# SCH__-_-__2023-09-22.net
KiCad netlist of a schematic drawn in EasyEDA
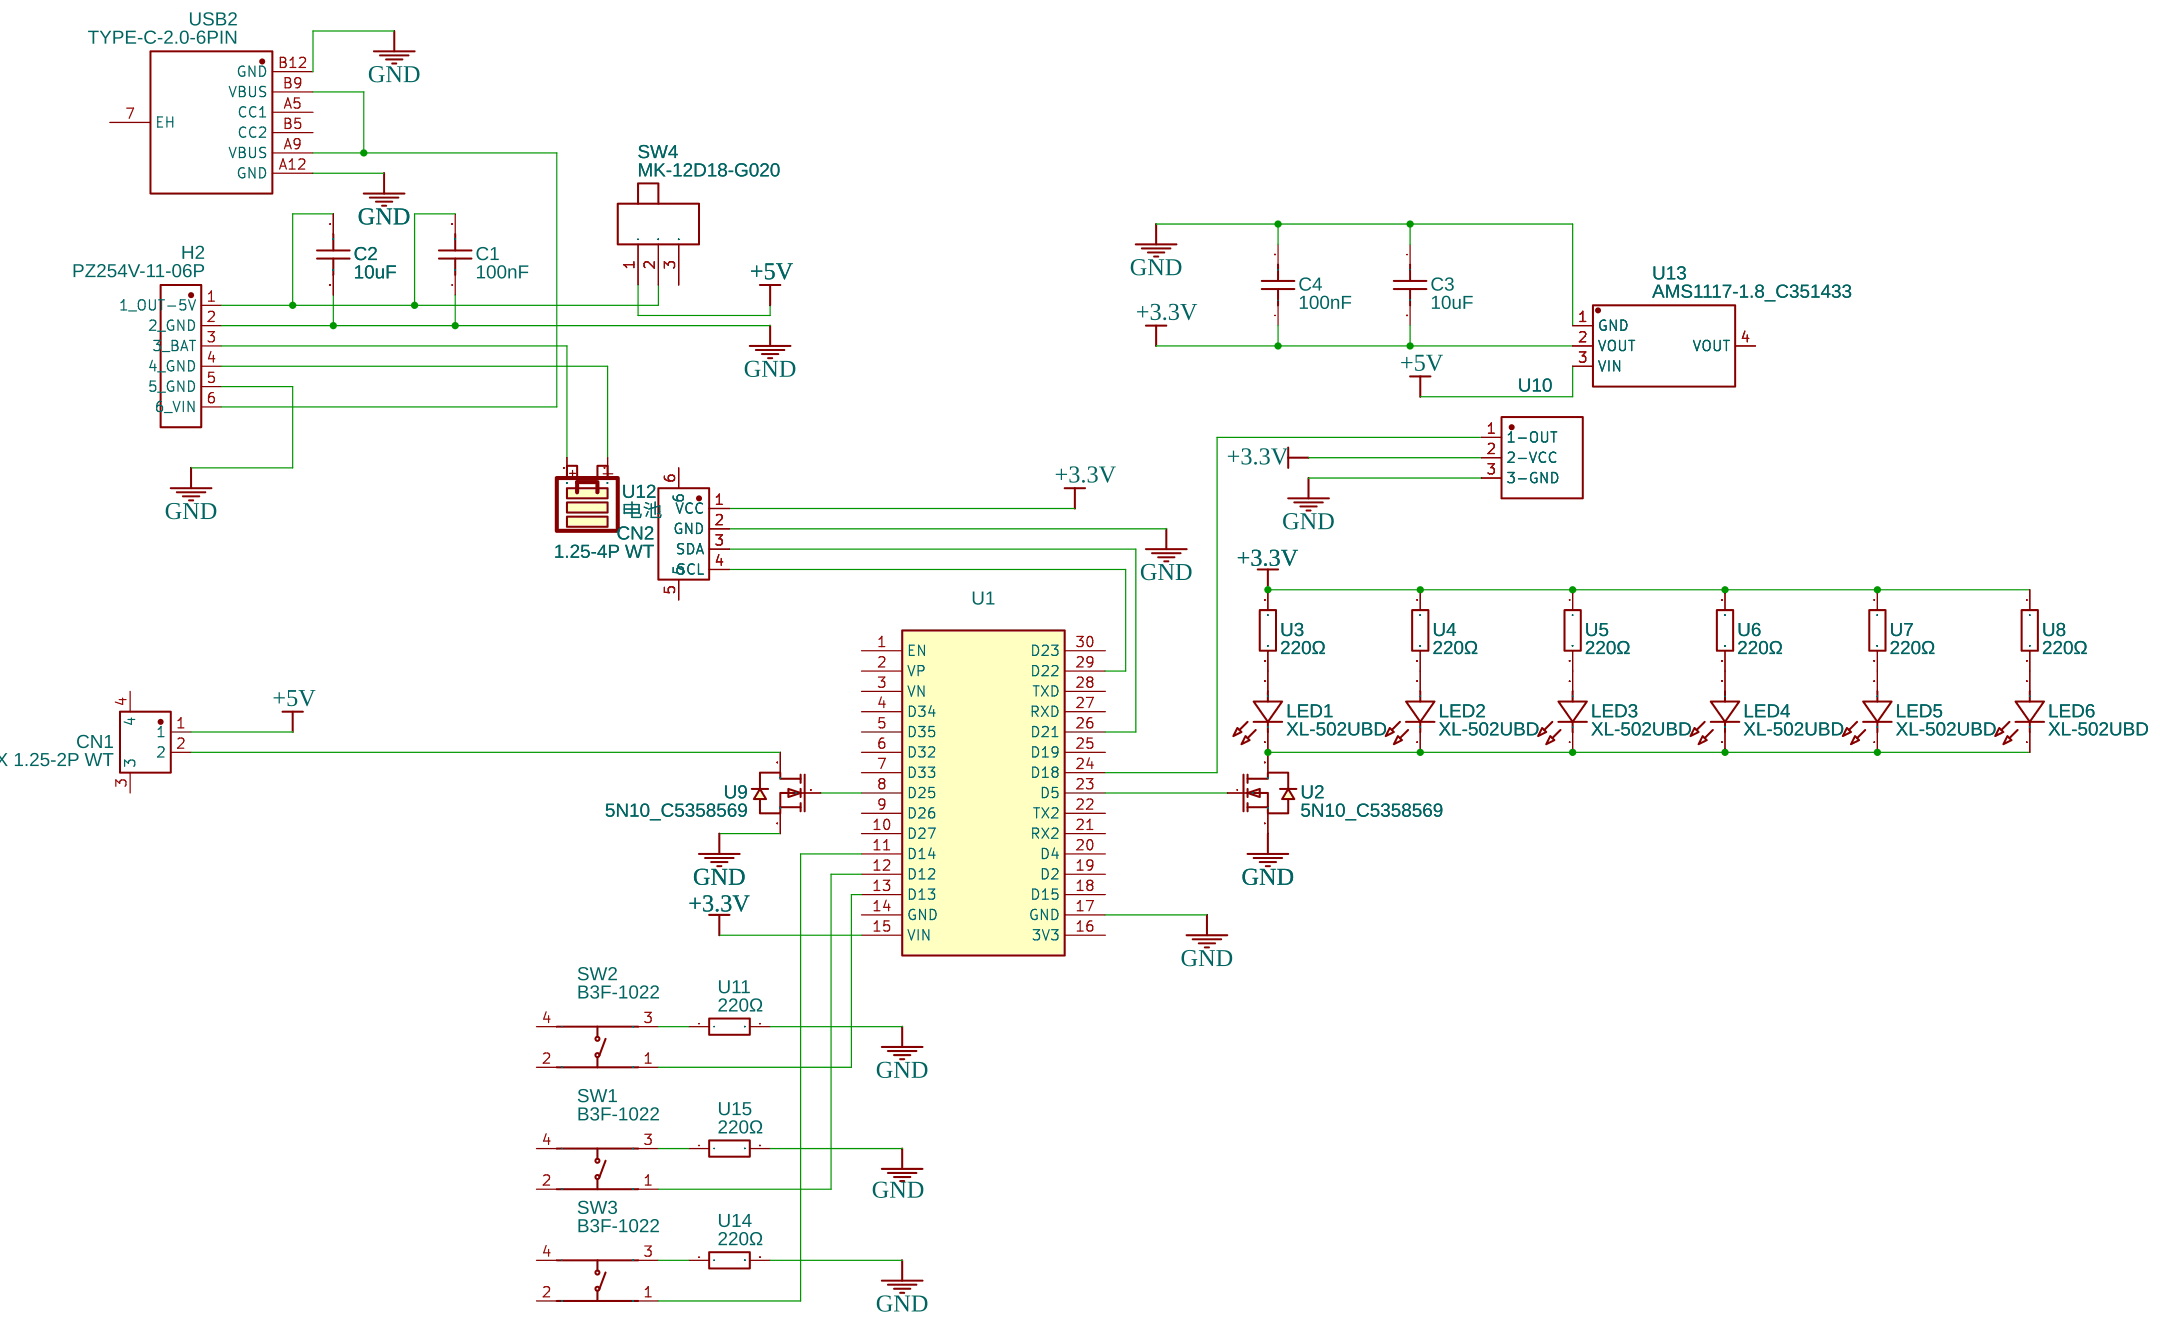
[diagram p0: schematic sheet]

(export (version "E")
  (design (tool "Eeschema 10.0.6"))
  (components
    (comp (ref "C1")
      (value "100nF")
      (fields
        (field (name "Manufacturer Part") "MC0603B104K500N8RH")
        (field (name "Manufacturer") "Sunway(信维通信)")
      )
      (libsource (lib "") (part "MC0603B104K500N8RH"))
    )
    (comp (ref "C2")
      (value "10uF")
      (fields (field (name "Manufacturer") "SAMSUNG(三星)"))
      (libsource (lib "") (part "10UF"))
    )
    (comp (ref "C3")
      (value "10uF")
      (fields (field (name "Manufacturer") "SAMSUNG(三星)"))
      (libsource (lib "") (part "10UF"))
    )
    (comp (ref "C4")
      (value "100nF")
      (fields
        (field (name "Manufacturer Part") "MC0603B104K500N8RH")
        (field (name "Manufacturer") "Sunway(信维通信)")
      )
      (libsource (lib "") (part "MC0603B104K500N8RH"))
    )
    (comp (ref "CN1")
      (value "HX 1.25-2P WT")
      (fields (field (name "Manufacturer") "hanxia(韩下)"))
      (libsource (lib "") (part "HX 1.25-2P WT"))
    )
    (comp (ref "CN2")
      (value "1.25-4P WT")
      (fields (field (name "Manufacturer") "SHOU HAN(首韩)"))
      (libsource (lib "") (part "1.25-4P WT"))
    )
    (comp (ref "H2")
      (value "PZ254V-11-06P")
      (fields (field (name "Manufacturer") "XFCN(兴飞)"))
      (libsource (lib "") (part "PZ254V-11-06P"))
    )
    (comp (ref "LED1")
      (value "XL-502UBD")
      (fields (field (name "Manufacturer") "XINGLIGHT(成兴光)"))
      (libsource (lib "") (part "XL-502UBD"))
    )
    (comp (ref "LED2")
      (value "XL-502UBD")
      (fields (field (name "Manufacturer") "XINGLIGHT(成兴光)"))
      (libsource (lib "") (part "XL-502UBD"))
    )
    (comp (ref "LED3")
      (value "XL-502UBD")
      (fields (field (name "Manufacturer") "XINGLIGHT(成兴光)"))
      (libsource (lib "") (part "XL-502UBD"))
    )
    (comp (ref "LED4")
      (value "XL-502UBD")
      (fields (field (name "Manufacturer") "XINGLIGHT(成兴光)"))
      (libsource (lib "") (part "XL-502UBD"))
    )
    (comp (ref "LED5")
      (value "XL-502UBD")
      (fields (field (name "Manufacturer") "XINGLIGHT(成兴光)"))
      (libsource (lib "") (part "XL-502UBD"))
    )
    (comp (ref "LED6")
      (value "XL-502UBD")
      (fields (field (name "Manufacturer") "XINGLIGHT(成兴光)"))
      (libsource (lib "") (part "XL-502UBD"))
    )
    (comp (ref "SW1")
      (value "B3F-1022")
      (fields (field (name "Manufacturer") "OMRON(欧姆龙)"))
      (libsource (lib "") (part "B3F-1022"))
    )
    (comp (ref "SW2")
      (value "B3F-1022")
      (fields (field (name "Manufacturer") "OMRON(欧姆龙)"))
      (libsource (lib "") (part "B3F-1022"))
    )
    (comp (ref "SW3")
      (value "B3F-1022")
      (fields (field (name "Manufacturer") "OMRON(欧姆龙)"))
      (libsource (lib "") (part "B3F-1022"))
    )
    (comp (ref "SW4")
      (value "MK-12D18-G020")
      (fields (field (name "Manufacturer") "G-Switch(品赞)"))
      (libsource (lib "") (part "MK-12D18-G020"))
    )
    (comp (ref "U1") (value "NO") (libsource (lib "") (part "ESP-WROOM-32")))
    (comp (ref "U2")
      (value "5N10_C5358569")
      (fields (field (name "Manufacturer Part") "5N10") (field (name "Manufacturer") "GOODWORK(固得沃克)"))
      (libsource (lib "") (part "5N10_C5358569_1"))
    )
    (comp (ref "U3")
      (value "220Ω")
      (fields (field (name "Manufacturer Part") "MF1/8W-220Ω±1%-ST52") (field (name "Manufacturer") "VO(翔胜)"))
      (libsource (lib "") (part "MF1/8W-220Ω±1%-ST52"))
    )
    (comp (ref "U4")
      (value "220Ω")
      (fields (field (name "Manufacturer Part") "MF1/8W-220Ω±1%-ST52") (field (name "Manufacturer") "VO(翔胜)"))
      (libsource (lib "") (part "MF1/8W-220Ω±1%-ST52"))
    )
    (comp (ref "U5")
      (value "220Ω")
      (fields (field (name "Manufacturer Part") "MF1/8W-220Ω±1%-ST52") (field (name "Manufacturer") "VO(翔胜)"))
      (libsource (lib "") (part "MF1/8W-220Ω±1%-ST52"))
    )
    (comp (ref "U6")
      (value "220Ω")
      (fields (field (name "Manufacturer Part") "MF1/8W-220Ω±1%-ST52") (field (name "Manufacturer") "VO(翔胜)"))
      (libsource (lib "") (part "MF1/8W-220Ω±1%-ST52"))
    )
    (comp (ref "U7")
      (value "220Ω")
      (fields (field (name "Manufacturer Part") "MF1/8W-220Ω±1%-ST52") (field (name "Manufacturer") "VO(翔胜)"))
      (libsource (lib "") (part "MF1/8W-220Ω±1%-ST52"))
    )
    (comp (ref "U8")
      (value "220Ω")
      (fields (field (name "Manufacturer Part") "MF1/8W-220Ω±1%-ST52") (field (name "Manufacturer") "VO(翔胜)"))
      (libsource (lib "") (part "MF1/8W-220Ω±1%-ST52"))
    )
    (comp (ref "U9")
      (value "5N10_C5358569")
      (fields (field (name "Manufacturer Part") "5N10") (field (name "Manufacturer") "GOODWORK(固得沃克)"))
      (libsource (lib "") (part "5N10_C5358569"))
    )
    (comp (ref "U10") (value "NO") (libsource (lib "") (part "SR602")))
    (comp (ref "U11")
      (value "220Ω")
      (fields (field (name "Manufacturer Part") "MF1/8W-220Ω±1%-ST52") (field (name "Manufacturer") "VO(翔胜)"))
      (libsource (lib "") (part "MF1/8W-220Ω±1%-ST52_1"))
    )
    (comp (ref "U12") (value "电池") (libsource (lib "") (part "电池")))
    (comp (ref "U13")
      (value "AMS1117-1.8_C351433")
      (fields (field (name "Manufacturer Part") "AMS1117-1.8") (field (name "Manufacturer") "PUOLOP(迪浦)"))
      (libsource (lib "") (part "AMS1117-1.8_C351433"))
    )
    (comp (ref "U14")
      (value "220Ω")
      (fields (field (name "Manufacturer Part") "MF1/8W-220Ω±1%-ST52") (field (name "Manufacturer") "VO(翔胜)"))
      (libsource (lib "") (part "MF1/8W-220Ω±1%-ST52_1"))
    )
    (comp (ref "U15")
      (value "220Ω")
      (fields (field (name "Manufacturer Part") "MF1/8W-220Ω±1%-ST52") (field (name "Manufacturer") "VO(翔胜)"))
      (libsource (lib "") (part "MF1/8W-220Ω±1%-ST52_1"))
    )
    (comp (ref "USB2")
      (value "TYPE-C-2.0-6PIN")
      (fields (field (name "Manufacturer Part") "Type-C-2.0-6Pin") (field (name "Manufacturer") "CIKI(皓富)"))
      (libsource (lib "") (part "TYPE-C-2.0-6PIN"))
    )
  )
  (nets
    (net (code "1") (name "+3.3V") (class "Default")
      (node (ref "C3") (pin "2") (pinfunction "2_2") (pintype "unspecified"))
      (node (ref "C4") (pin "1") (pinfunction "1_1") (pintype "unspecified"))
      (node (ref "CN2") (pin "1") (pinfunction "VCC_1") (pintype "unspecified"))
      (node (ref "U1") (pin "15") (pinfunction "VIN_15") (pintype "unspecified"))
      (node (ref "U10") (pin "2") (pinfunction "2-VCC_2") (pintype "unspecified"))
      (node (ref "U13") (pin "2") (pinfunction "VOUT_2") (pintype "unspecified"))
      (node (ref "U3") (pin "1") (pinfunction "1_1") (pintype "unspecified"))
      (node (ref "U4") (pin "1") (pinfunction "1_1") (pintype "unspecified"))
      (node (ref "U5") (pin "1") (pinfunction "1_1") (pintype "unspecified"))
      (node (ref "U6") (pin "1") (pinfunction "1_1") (pintype "unspecified"))
      (node (ref "U7") (pin "1") (pinfunction "1_1") (pintype "unspecified"))
      (node (ref "U8") (pin "1") (pinfunction "1_1") (pintype "unspecified"))
    )
    (net (code "2") (name "+5V") (class "Default")
      (node (ref "CN1") (pin "1") (pinfunction "1_1") (pintype "unspecified"))
      (node (ref "SW4") (pin "1") (pinfunction "1_1") (pintype "unspecified"))
      (node (ref "U13") (pin "3") (pinfunction "VIN_3") (pintype "unspecified"))
    )
    (net (code "3") (name "GND") (class "Default")
      (node (ref "C1") (pin "1") (pinfunction "1_1") (pintype "unspecified"))
      (node (ref "C2") (pin "2") (pinfunction "2_2") (pintype "unspecified"))
      (node (ref "C3") (pin "1") (pinfunction "1_1") (pintype "unspecified"))
      (node (ref "C4") (pin "2") (pinfunction "2_2") (pintype "unspecified"))
      (node (ref "CN2") (pin "2") (pinfunction "GND_2") (pintype "unspecified"))
      (node (ref "H2") (pin "2") (pinfunction "2_GND_2") (pintype "unspecified"))
      (node (ref "H2") (pin "5") (pinfunction "5_GND_5") (pintype "unspecified"))
      (node (ref "U1") (pin "17") (pinfunction "GND_17") (pintype "unspecified"))
      (node (ref "U10") (pin "3") (pinfunction "3-GND_3") (pintype "unspecified"))
      (node (ref "U11") (pin "2") (pinfunction "2_2") (pintype "unspecified"))
      (node (ref "U13") (pin "1") (pinfunction "GND_1") (pintype "unspecified"))
      (node (ref "U14") (pin "2") (pinfunction "2_2") (pintype "unspecified"))
      (node (ref "U15") (pin "2") (pinfunction "2_2") (pintype "unspecified"))
      (node (ref "U2") (pin "2") (pinfunction "S_2") (pintype "unspecified"))
      (node (ref "U9") (pin "2") (pinfunction "S_2") (pintype "unspecified"))
      (node (ref "USB2") (pin "A12") (pinfunction "GND_A12") (pintype "unspecified"))
      (node (ref "USB2") (pin "B12") (pinfunction "GND_B12") (pintype "unspecified"))
    )
    (net (code "4") (name "Net-(CN2-SCL)") (class "Default")
      (node (ref "CN2") (pin "4") (pinfunction "SCL_4") (pintype "unspecified"))
      (node (ref "U1") (pin "29") (pinfunction "D22_29") (pintype "unspecified"))
    )
    (net (code "5") (name "Net-(CN2-SDA)") (class "Default")
      (node (ref "CN2") (pin "3") (pinfunction "SDA_3") (pintype "unspecified"))
      (node (ref "U1") (pin "26") (pinfunction "D21_26") (pintype "unspecified"))
    )
    (net (code "6") (name "Net-(H2-1_OUT-5V)") (class "Default")
      (node (ref "C1") (pin "2") (pinfunction "2_2") (pintype "unspecified"))
      (node (ref "C2") (pin "1") (pinfunction "1_1") (pintype "unspecified"))
      (node (ref "H2") (pin "1") (pinfunction "1_OUT-5V_1") (pintype "unspecified"))
      (node (ref "SW4") (pin "2") (pinfunction "2_2") (pintype "unspecified"))
    )
    (net (code "7") (name "Net-(H2-3_BAT)") (class "Default")
      (node (ref "H2") (pin "3") (pinfunction "3_BAT_3") (pintype "unspecified"))
      (node (ref "U12") (pin "1") (pinfunction "1_1") (pintype "unspecified"))
    )
    (net (code "8") (name "Net-(H2-4_GND)") (class "Default")
      (node (ref "H2") (pin "4") (pinfunction "4_GND_4") (pintype "unspecified"))
      (node (ref "U12") (pin "2") (pinfunction "2_2") (pintype "unspecified"))
    )
    (net (code "9") (name "Net-(H2-6_VIN)") (class "Default")
      (node (ref "H2") (pin "6") (pinfunction "6_VIN_6") (pintype "unspecified"))
      (node (ref "USB2") (pin "A9") (pinfunction "VBUS_A9") (pintype "unspecified"))
      (node (ref "USB2") (pin "B9") (pinfunction "VBUS_B9") (pintype "unspecified"))
    )
    (net (code "10") (name "Net-(LED1-A)") (class "Default")
      (node (ref "LED1") (pin "2") (pinfunction "A_2") (pintype "unspecified"))
      (node (ref "U3") (pin "2") (pinfunction "2_2") (pintype "unspecified"))
    )
    (net (code "11") (name "Net-(LED1-K)") (class "Default")
      (node (ref "LED1") (pin "1") (pinfunction "K_1") (pintype "unspecified"))
      (node (ref "LED2") (pin "1") (pinfunction "K_1") (pintype "unspecified"))
      (node (ref "LED3") (pin "1") (pinfunction "K_1") (pintype "unspecified"))
      (node (ref "LED4") (pin "1") (pinfunction "K_1") (pintype "unspecified"))
      (node (ref "LED5") (pin "1") (pinfunction "K_1") (pintype "unspecified"))
      (node (ref "LED6") (pin "1") (pinfunction "K_1") (pintype "unspecified"))
      (node (ref "U2") (pin "3") (pinfunction "D_3") (pintype "unspecified"))
    )
    (net (code "12") (name "Net-(LED2-A)") (class "Default")
      (node (ref "LED2") (pin "2") (pinfunction "A_2") (pintype "unspecified"))
      (node (ref "U4") (pin "2") (pinfunction "2_2") (pintype "unspecified"))
    )
    (net (code "13") (name "Net-(LED3-A)") (class "Default")
      (node (ref "LED3") (pin "2") (pinfunction "A_2") (pintype "unspecified"))
      (node (ref "U5") (pin "2") (pinfunction "2_2") (pintype "unspecified"))
    )
    (net (code "14") (name "Net-(LED4-A)") (class "Default")
      (node (ref "LED4") (pin "2") (pinfunction "A_2") (pintype "unspecified"))
      (node (ref "U6") (pin "2") (pinfunction "2_2") (pintype "unspecified"))
    )
    (net (code "15") (name "Net-(LED5-A)") (class "Default")
      (node (ref "LED5") (pin "2") (pinfunction "A_2") (pintype "unspecified"))
      (node (ref "U7") (pin "2") (pinfunction "2_2") (pintype "unspecified"))
    )
    (net (code "16") (name "Net-(LED6-A)") (class "Default")
      (node (ref "LED6") (pin "2") (pinfunction "A_2") (pintype "unspecified"))
      (node (ref "U8") (pin "2") (pinfunction "2_2") (pintype "unspecified"))
    )
    (net (code "17") (name "Net-(SW1-Pad3)") (class "Default")
      (node (ref "SW1") (pin "3") (pinfunction "3_3") (pintype "unspecified"))
      (node (ref "U15") (pin "1") (pinfunction "1_1") (pintype "unspecified"))
    )
    (net (code "18") (name "Net-(SW2-Pad3)") (class "Default")
      (node (ref "SW2") (pin "3") (pinfunction "3_3") (pintype "unspecified"))
      (node (ref "U11") (pin "1") (pinfunction "1_1") (pintype "unspecified"))
    )
    (net (code "19") (name "Net-(SW3-Pad3)") (class "Default")
      (node (ref "SW3") (pin "3") (pinfunction "3_3") (pintype "unspecified"))
      (node (ref "U14") (pin "1") (pinfunction "1_1") (pintype "unspecified"))
    )
    (net (code "20") (name "Net-(U1-D5)") (class "Default")
      (node (ref "U1") (pin "23") (pinfunction "D5_23") (pintype "unspecified"))
      (node (ref "U2") (pin "1") (pinfunction "G_1") (pintype "unspecified"))
    )
    (net (code "21") (name "Net-(U1-D12)") (class "Default")
      (node (ref "SW1") (pin "1") (pinfunction "1_1") (pintype "unspecified"))
      (node (ref "U1") (pin "12") (pinfunction "D12_12") (pintype "unspecified"))
    )
    (net (code "22") (name "Net-(U1-D13)") (class "Default")
      (node (ref "SW2") (pin "1") (pinfunction "1_1") (pintype "unspecified"))
      (node (ref "U1") (pin "13") (pinfunction "D13_13") (pintype "unspecified"))
    )
    (net (code "23") (name "Net-(U1-D14)") (class "Default")
      (node (ref "SW3") (pin "1") (pinfunction "1_1") (pintype "unspecified"))
      (node (ref "U1") (pin "11") (pinfunction "D14_11") (pintype "unspecified"))
    )
    (net (code "24") (name "Net-(U1-D18)") (class "Default")
      (node (ref "U1") (pin "24") (pinfunction "D18_24") (pintype "unspecified"))
      (node (ref "U10") (pin "1") (pinfunction "1-OUT_1") (pintype "unspecified"))
    )
    (net (code "25") (name "Net-(U1-D25)") (class "Default")
      (node (ref "U1") (pin "8") (pinfunction "D25_8") (pintype "unspecified"))
      (node (ref "U9") (pin "1") (pinfunction "G_1") (pintype "unspecified"))
    )
    (net (code "26") (name "Net-(U9-D)") (class "Default")
      (node (ref "CN1") (pin "2") (pinfunction "2_2") (pintype "unspecified"))
      (node (ref "U9") (pin "3") (pinfunction "D_3") (pintype "unspecified"))
    )
    (net (code "27") (name "unconnected-(CN1-Pad3)") (class "Default")
      (node (ref "CN1") (pin "3") (pinfunction "3_3") (pintype "unspecified"))
    )
    (net (code "28") (name "unconnected-(CN1-Pad4)") (class "Default")
      (node (ref "CN1") (pin "4") (pinfunction "4_4") (pintype "unspecified"))
    )
    (net (code "29") (name "unconnected-(CN2-Pad5)") (class "Default")
      (node (ref "CN2") (pin "5") (pinfunction "5_5") (pintype "unspecified"))
    )
    (net (code "30") (name "unconnected-(CN2-Pad6)") (class "Default")
      (node (ref "CN2") (pin "6") (pinfunction "6_6") (pintype "unspecified"))
    )
    (net (code "31") (name "unconnected-(SW1-Pad2)") (class "Default")
      (node (ref "SW1") (pin "2") (pinfunction "2_2") (pintype "unspecified"))
    )
    (net (code "32") (name "unconnected-(SW1-Pad4)") (class "Default")
      (node (ref "SW1") (pin "4") (pinfunction "4_4") (pintype "unspecified"))
    )
    (net (code "33") (name "unconnected-(SW2-Pad2)") (class "Default")
      (node (ref "SW2") (pin "2") (pinfunction "2_2") (pintype "unspecified"))
    )
    (net (code "34") (name "unconnected-(SW2-Pad4)") (class "Default")
      (node (ref "SW2") (pin "4") (pinfunction "4_4") (pintype "unspecified"))
    )
    (net (code "35") (name "unconnected-(SW3-Pad2)") (class "Default")
      (node (ref "SW3") (pin "2") (pinfunction "2_2") (pintype "unspecified"))
    )
    (net (code "36") (name "unconnected-(SW3-Pad4)") (class "Default")
      (node (ref "SW3") (pin "4") (pinfunction "4_4") (pintype "unspecified"))
    )
    (net (code "37") (name "unconnected-(SW4-Pad3)") (class "Default")
      (node (ref "SW4") (pin "3") (pinfunction "3_3") (pintype "unspecified"))
    )
    (net (code "38") (name "unconnected-(U1-3V3-Pad16)") (class "Default")
      (node (ref "U1") (pin "16") (pinfunction "3V3_16") (pintype "unspecified"))
    )
    (net (code "39") (name "unconnected-(U1-D2-Pad19)") (class "Default")
      (node (ref "U1") (pin "19") (pinfunction "D2_19") (pintype "unspecified"))
    )
    (net (code "40") (name "unconnected-(U1-D4-Pad20)") (class "Default")
      (node (ref "U1") (pin "20") (pinfunction "D4_20") (pintype "unspecified"))
    )
    (net (code "41") (name "unconnected-(U1-D15-Pad18)") (class "Default")
      (node (ref "U1") (pin "18") (pinfunction "D15_18") (pintype "unspecified"))
    )
    (net (code "42") (name "unconnected-(U1-D19-Pad25)") (class "Default")
      (node (ref "U1") (pin "25") (pinfunction "D19_25") (pintype "unspecified"))
    )
    (net (code "43") (name "unconnected-(U1-D23-Pad30)") (class "Default")
      (node (ref "U1") (pin "30") (pinfunction "D23_30") (pintype "unspecified"))
    )
    (net (code "44") (name "unconnected-(U1-D26-Pad9)") (class "Default")
      (node (ref "U1") (pin "9") (pinfunction "D26_9") (pintype "unspecified"))
    )
    (net (code "45") (name "unconnected-(U1-D27-Pad10)") (class "Default")
      (node (ref "U1") (pin "10") (pinfunction "D27_10") (pintype "unspecified"))
    )
    (net (code "46") (name "unconnected-(U1-D32-Pad6)") (class "Default")
      (node (ref "U1") (pin "6") (pinfunction "D32_6") (pintype "unspecified"))
    )
    (net (code "47") (name "unconnected-(U1-D33-Pad7)") (class "Default")
      (node (ref "U1") (pin "7") (pinfunction "D33_7") (pintype "unspecified"))
    )
    (net (code "48") (name "unconnected-(U1-D34-Pad4)") (class "Default")
      (node (ref "U1") (pin "4") (pinfunction "D34_4") (pintype "unspecified"))
    )
    (net (code "49") (name "unconnected-(U1-D35-Pad5)") (class "Default")
      (node (ref "U1") (pin "5") (pinfunction "D35_5") (pintype "unspecified"))
    )
    (net (code "50") (name "unconnected-(U1-EN-Pad1)") (class "Default")
      (node (ref "U1") (pin "1") (pinfunction "EN_1") (pintype "unspecified"))
    )
    (net (code "51") (name "unconnected-(U1-GND-Pad14)") (class "Default")
      (node (ref "U1") (pin "14") (pinfunction "GND_14") (pintype "unspecified"))
    )
    (net (code "52") (name "unconnected-(U1-RX2-Pad21)") (class "Default")
      (node (ref "U1") (pin "21") (pinfunction "RX2_21") (pintype "unspecified"))
    )
    (net (code "53") (name "unconnected-(U1-RXD-Pad27)") (class "Default")
      (node (ref "U1") (pin "27") (pinfunction "RXD_27") (pintype "unspecified"))
    )
    (net (code "54") (name "unconnected-(U1-TX2-Pad22)") (class "Default")
      (node (ref "U1") (pin "22") (pinfunction "TX2_22") (pintype "unspecified"))
    )
    (net (code "55") (name "unconnected-(U1-TXD-Pad28)") (class "Default")
      (node (ref "U1") (pin "28") (pinfunction "TXD_28") (pintype "unspecified"))
    )
    (net (code "56") (name "unconnected-(U1-VN-Pad3)") (class "Default")
      (node (ref "U1") (pin "3") (pinfunction "VN_3") (pintype "unspecified"))
    )
    (net (code "57") (name "unconnected-(U1-VP-Pad2)") (class "Default")
      (node (ref "U1") (pin "2") (pinfunction "VP_2") (pintype "unspecified"))
    )
    (net (code "58") (name "unconnected-(U13-VOUT-Pad4)") (class "Default")
      (node (ref "U13") (pin "4") (pinfunction "VOUT_4") (pintype "unspecified"))
    )
    (net (code "59") (name "unconnected-(USB2-CC1-PadA5)") (class "Default")
      (node (ref "USB2") (pin "A5") (pinfunction "CC1_A5") (pintype "unspecified"))
    )
    (net (code "60") (name "unconnected-(USB2-CC2-PadB5)") (class "Default")
      (node (ref "USB2") (pin "B5") (pinfunction "CC2_B5") (pintype "unspecified"))
    )
    (net (code "61") (name "unconnected-(USB2-EH-Pad7)") (class "Default")
      (node (ref "USB2") (pin "7") (pinfunction "EH_7") (pintype "unspecified"))
    )
  )
)
